# Schematic.net
KiCad netlist of a schematic drawn in Altium Designer
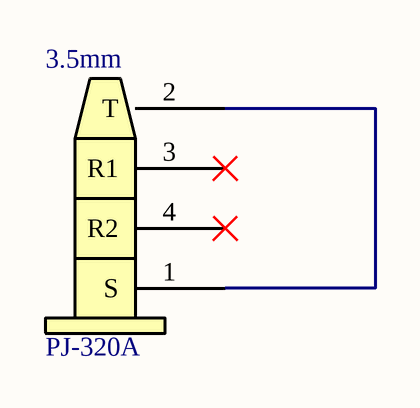
[diagram p0: Schematic.SchDoc]

(export (version "E")
  (design (tool "Eeschema 10.0.6"))
  (components
    (comp (ref "3.5mm")
      (value "PJ-320A")
      (description "A thru hole 3.5mm TRRS audio jack connector")
      (libsource (lib "SSPACE") (part "PJ-320A"))
    )
  )
  (nets
    (net (code "1") (name "Net-(3.5mm-S)") (class "Default")
      (node (ref "3.5mm") (pin "1") (pinfunction "S_1") (pintype "passive"))
      (node (ref "3.5mm") (pin "2") (pinfunction "T_2") (pintype "passive"))
    )
    (net (code "2") (name "unconnected-(3.5mm-R1-Pad3)") (class "Default")
      (node (ref "3.5mm") (pin "3") (pinfunction "R1_3") (pintype "passive+no_connect"))
    )
    (net (code "3") (name "unconnected-(3.5mm-R2-Pad4)") (class "Default")
      (node (ref "3.5mm") (pin "4") (pinfunction "R2_4") (pintype "passive+no_connect"))
    )
  )
)
